# QFN28_3mm_v1_0.net
KiCad netlist of a schematic drawn in EAGLE
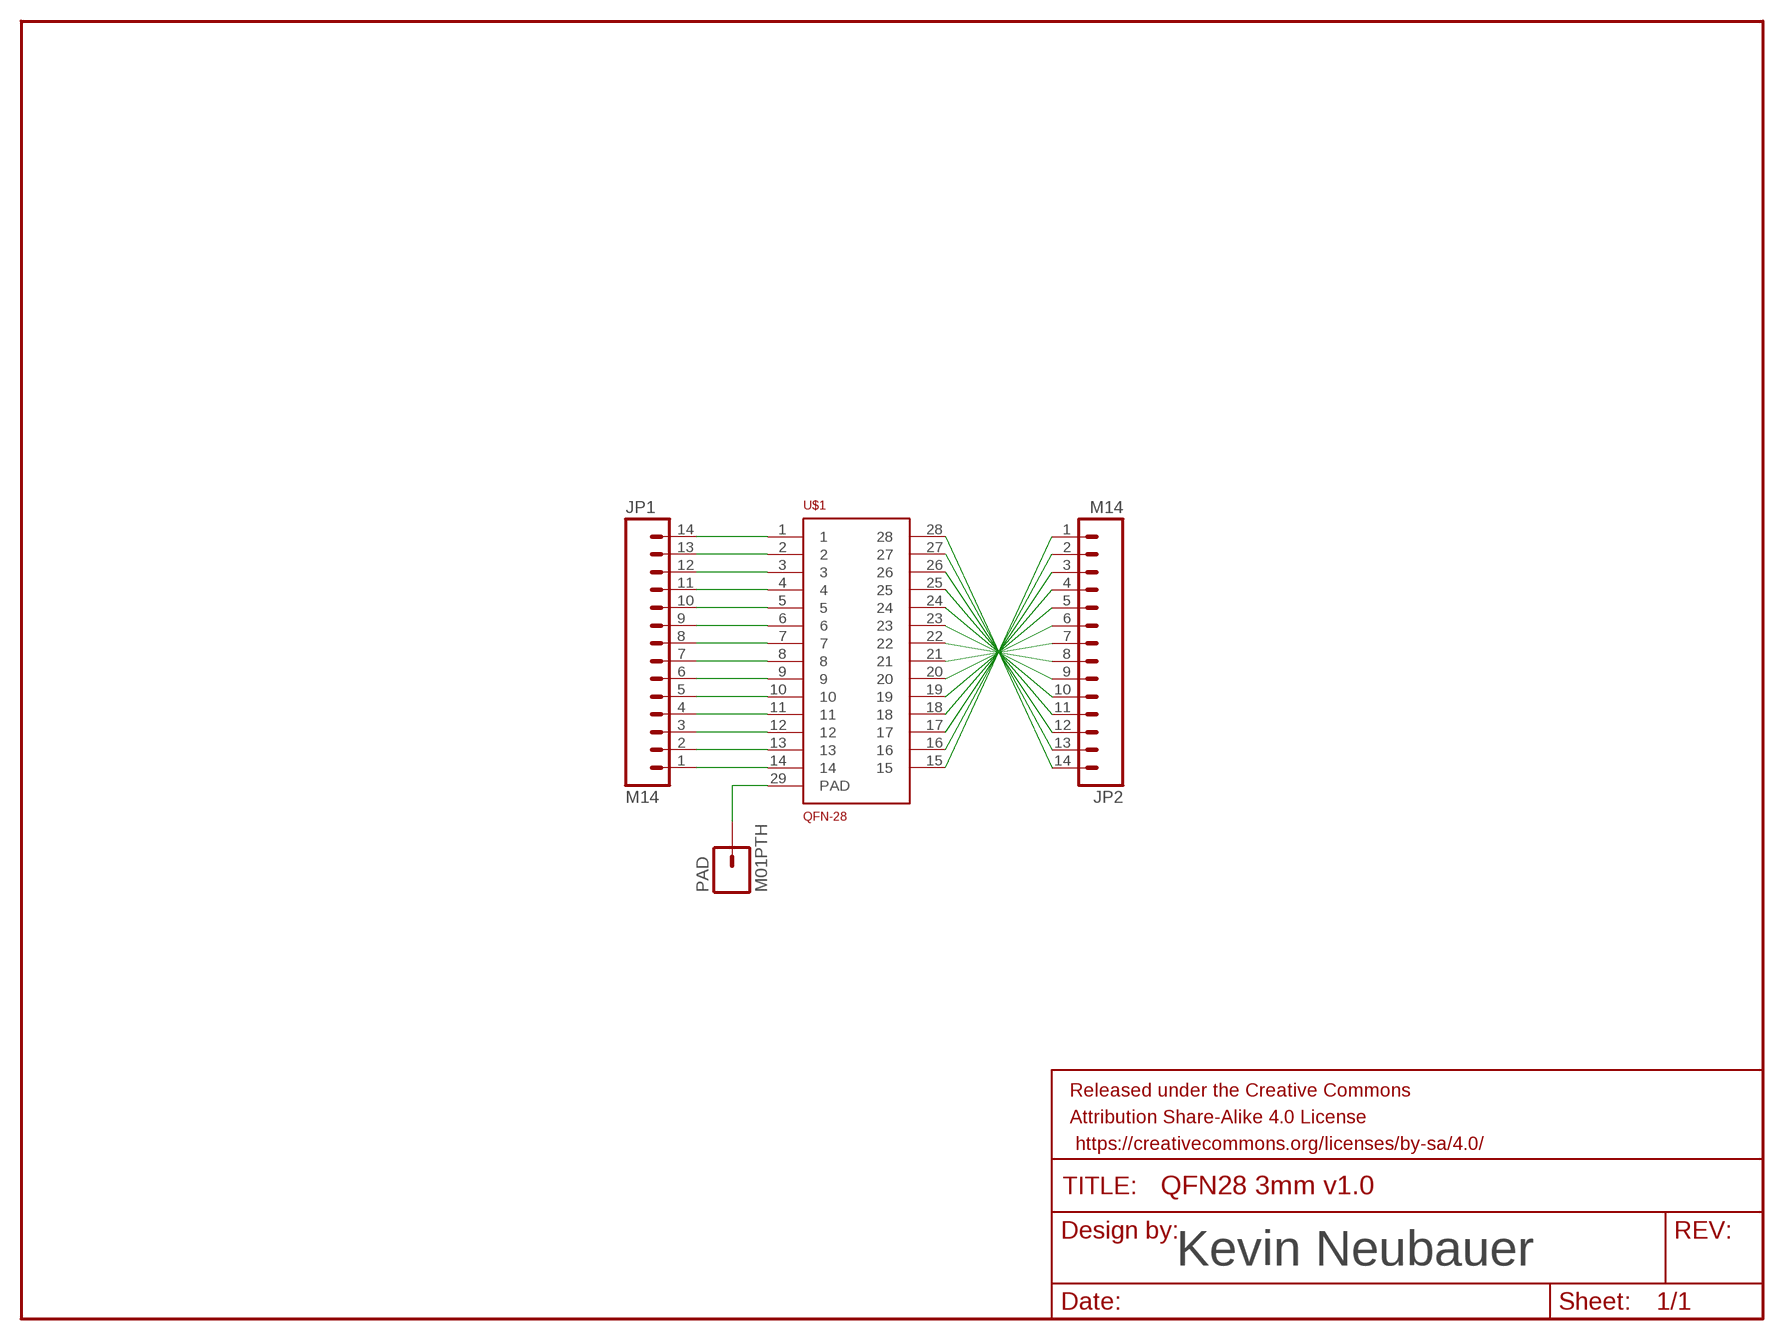
[diagram p0: schematic, sheet 1]

(export (version "E")
  (design (tool "Eeschema 10.0.6"))
  (components
    (comp (ref "FRAME1")
      (value "FRAME-LETTER")
      (footprint "eagle-import:CREATIVE_COMMONS")
      (libsource (lib "eagle-import") (part "FRAME-LETTER"))
    )
    (comp (ref "JP1")
      (value "M14")
      (footprint "eagle-import:1X14")
      (libsource (lib "eagle-import") (part "M14"))
    )
    (comp (ref "JP2")
      (value "M14")
      (footprint "eagle-import:1X14")
      (libsource (lib "eagle-import") (part "M14"))
    )
    (comp (ref "PAD")
      (value "M01PTH")
      (footprint "eagle-import:1X01")
      (libsource (lib "eagle-import") (part "M01PTH"))
    )
    (comp (ref "U$1")
      (value "QFN-28")
      (footprint "eagle-import:QFN-28")
      (libsource (lib "eagle-import") (part "QFN-28"))
    )
  )
  (nets
    (net (code "1") (name "Net-(JP1-Pad1)") (class "Default")
      (node (ref "JP1") (pin "1") (pinfunction "1_1") (pintype "passive"))
      (node (ref "U$1") (pin "14") (pinfunction "14_14") (pintype "bidirectional"))
    )
    (net (code "2") (name "Net-(JP1-Pad2)") (class "Default")
      (node (ref "JP1") (pin "2") (pinfunction "2_2") (pintype "passive"))
      (node (ref "U$1") (pin "13") (pinfunction "13_13") (pintype "bidirectional"))
    )
    (net (code "3") (name "Net-(JP1-Pad3)") (class "Default")
      (node (ref "JP1") (pin "3") (pinfunction "3_3") (pintype "passive"))
      (node (ref "U$1") (pin "12") (pinfunction "12_12") (pintype "bidirectional"))
    )
    (net (code "4") (name "Net-(JP1-Pad4)") (class "Default")
      (node (ref "JP1") (pin "4") (pinfunction "4_4") (pintype "passive"))
      (node (ref "U$1") (pin "11") (pinfunction "11_11") (pintype "bidirectional"))
    )
    (net (code "5") (name "Net-(JP1-Pad5)") (class "Default")
      (node (ref "JP1") (pin "5") (pinfunction "5_5") (pintype "passive"))
      (node (ref "U$1") (pin "10") (pinfunction "10_10") (pintype "bidirectional"))
    )
    (net (code "6") (name "Net-(JP1-Pad6)") (class "Default")
      (node (ref "JP1") (pin "6") (pinfunction "6_6") (pintype "passive"))
      (node (ref "U$1") (pin "9") (pinfunction "9_9") (pintype "bidirectional"))
    )
    (net (code "7") (name "Net-(JP1-Pad7)") (class "Default")
      (node (ref "JP1") (pin "7") (pinfunction "7_7") (pintype "passive"))
      (node (ref "U$1") (pin "8") (pinfunction "8_8") (pintype "bidirectional"))
    )
    (net (code "8") (name "Net-(JP1-Pad8)") (class "Default")
      (node (ref "JP1") (pin "8") (pinfunction "8_8") (pintype "passive"))
      (node (ref "U$1") (pin "7") (pinfunction "7_7") (pintype "bidirectional"))
    )
    (net (code "9") (name "Net-(JP1-Pad9)") (class "Default")
      (node (ref "JP1") (pin "9") (pinfunction "9_9") (pintype "passive"))
      (node (ref "U$1") (pin "6") (pinfunction "6_6") (pintype "bidirectional"))
    )
    (net (code "10") (name "Net-(JP1-Pad10)") (class "Default")
      (node (ref "JP1") (pin "10") (pinfunction "10_10") (pintype "passive"))
      (node (ref "U$1") (pin "5") (pinfunction "5_5") (pintype "bidirectional"))
    )
    (net (code "11") (name "Net-(JP1-Pad11)") (class "Default")
      (node (ref "JP1") (pin "11") (pinfunction "11_11") (pintype "passive"))
      (node (ref "U$1") (pin "4") (pinfunction "4_4") (pintype "bidirectional"))
    )
    (net (code "12") (name "Net-(JP1-Pad12)") (class "Default")
      (node (ref "JP1") (pin "12") (pinfunction "12_12") (pintype "passive"))
      (node (ref "U$1") (pin "3") (pinfunction "3_3") (pintype "bidirectional"))
    )
    (net (code "13") (name "Net-(JP1-Pad13)") (class "Default")
      (node (ref "JP1") (pin "13") (pinfunction "13_13") (pintype "passive"))
      (node (ref "U$1") (pin "2") (pinfunction "2_2") (pintype "bidirectional"))
    )
    (net (code "14") (name "Net-(JP1-Pad14)") (class "Default")
      (node (ref "JP1") (pin "14") (pinfunction "14_14") (pintype "passive"))
      (node (ref "U$1") (pin "1") (pinfunction "1_1") (pintype "bidirectional"))
    )
    (net (code "15") (name "Net-(JP2-Pad1)") (class "Default")
      (node (ref "JP2") (pin "1") (pinfunction "1_1") (pintype "passive"))
      (node (ref "U$1") (pin "15") (pinfunction "15_15") (pintype "bidirectional"))
    )
    (net (code "16") (name "Net-(JP2-Pad2)") (class "Default")
      (node (ref "JP2") (pin "2") (pinfunction "2_2") (pintype "passive"))
      (node (ref "U$1") (pin "16") (pinfunction "16_16") (pintype "bidirectional"))
    )
    (net (code "17") (name "Net-(JP2-Pad3)") (class "Default")
      (node (ref "JP2") (pin "3") (pinfunction "3_3") (pintype "passive"))
      (node (ref "U$1") (pin "17") (pinfunction "17_17") (pintype "bidirectional"))
    )
    (net (code "18") (name "Net-(JP2-Pad4)") (class "Default")
      (node (ref "JP2") (pin "4") (pinfunction "4_4") (pintype "passive"))
      (node (ref "U$1") (pin "18") (pinfunction "18_18") (pintype "bidirectional"))
    )
    (net (code "19") (name "Net-(JP2-Pad5)") (class "Default")
      (node (ref "JP2") (pin "5") (pinfunction "5_5") (pintype "passive"))
      (node (ref "U$1") (pin "19") (pinfunction "19_19") (pintype "bidirectional"))
    )
    (net (code "20") (name "Net-(JP2-Pad6)") (class "Default")
      (node (ref "JP2") (pin "6") (pinfunction "6_6") (pintype "passive"))
      (node (ref "U$1") (pin "20") (pinfunction "20_20") (pintype "bidirectional"))
    )
    (net (code "21") (name "Net-(JP2-Pad7)") (class "Default")
      (node (ref "JP2") (pin "7") (pinfunction "7_7") (pintype "passive"))
      (node (ref "U$1") (pin "21") (pinfunction "21_21") (pintype "bidirectional"))
    )
    (net (code "22") (name "Net-(JP2-Pad8)") (class "Default")
      (node (ref "JP2") (pin "8") (pinfunction "8_8") (pintype "passive"))
      (node (ref "U$1") (pin "22") (pinfunction "22_22") (pintype "bidirectional"))
    )
    (net (code "23") (name "Net-(JP2-Pad9)") (class "Default")
      (node (ref "JP2") (pin "9") (pinfunction "9_9") (pintype "passive"))
      (node (ref "U$1") (pin "23") (pinfunction "23_23") (pintype "bidirectional"))
    )
    (net (code "24") (name "Net-(JP2-Pad10)") (class "Default")
      (node (ref "JP2") (pin "10") (pinfunction "10_10") (pintype "passive"))
      (node (ref "U$1") (pin "24") (pinfunction "24_24") (pintype "bidirectional"))
    )
    (net (code "25") (name "Net-(JP2-Pad11)") (class "Default")
      (node (ref "JP2") (pin "11") (pinfunction "11_11") (pintype "passive"))
      (node (ref "U$1") (pin "25") (pinfunction "25_25") (pintype "bidirectional"))
    )
    (net (code "26") (name "Net-(JP2-Pad12)") (class "Default")
      (node (ref "JP2") (pin "12") (pinfunction "12_12") (pintype "passive"))
      (node (ref "U$1") (pin "26") (pinfunction "26_26") (pintype "bidirectional"))
    )
    (net (code "27") (name "Net-(JP2-Pad13)") (class "Default")
      (node (ref "JP2") (pin "13") (pinfunction "13_13") (pintype "passive"))
      (node (ref "U$1") (pin "27") (pinfunction "27_27") (pintype "bidirectional"))
    )
    (net (code "28") (name "Net-(JP2-Pad14)") (class "Default")
      (node (ref "JP2") (pin "14") (pinfunction "14_14") (pintype "passive"))
      (node (ref "U$1") (pin "28") (pinfunction "28_28") (pintype "bidirectional"))
    )
    (net (code "29") (name "Net-(U$1-PAD)") (class "Default")
      (node (ref "PAD") (pin "1") (pinfunction "1_1") (pintype "passive"))
      (node (ref "U$1") (pin "29") (pinfunction "PAD_29") (pintype "bidirectional"))
    )
  )
)
